# aquaPh.net
KiCad netlist of a schematic drawn in EAGLE
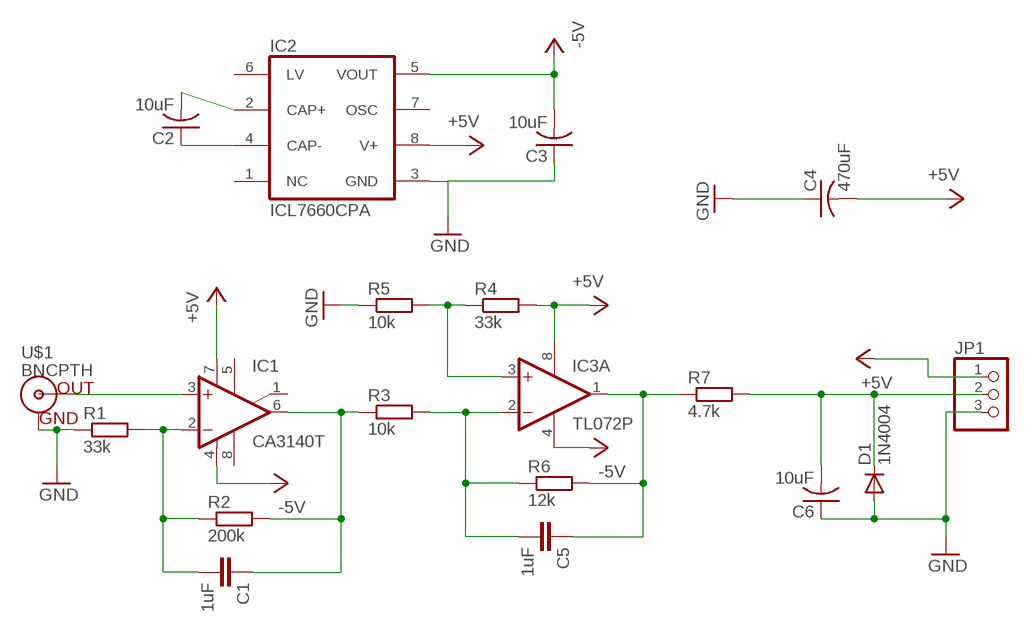
[diagram p0: schematic, sheet 1]

(export (version "E")
  (design (tool "Eeschema 10.0.6"))
  (components
    (comp (ref "C1")
      (value "1uF")
      (footprint "eagle-import:C050-035X075")
      (libsource (lib "eagle-import") (part "C-EU050-035X075"))
    )
    (comp (ref "C2")
      (value "10uF")
      (footprint "eagle-import:C075-042X103")
      (libsource (lib "eagle-import") (part "C-US075-042X103"))
    )
    (comp (ref "C3")
      (value "10uF")
      (footprint "eagle-import:C075-042X103")
      (libsource (lib "eagle-import") (part "C-US075-042X103"))
    )
    (comp (ref "C4")
      (value "470uF")
      (footprint "eagle-import:C075-042X103")
      (libsource (lib "eagle-import") (part "C-US075-042X103"))
    )
    (comp (ref "C5")
      (value "1uF")
      (footprint "eagle-import:C050-035X075")
      (libsource (lib "eagle-import") (part "C-EU050-035X075"))
    )
    (comp (ref "C6")
      (value "10uF")
      (footprint "eagle-import:C075-042X103")
      (libsource (lib "eagle-import") (part "C-US075-042X103"))
    )
    (comp (ref "D1")
      (value "1N4004")
      (footprint "eagle-import:DO41-10")
      (libsource (lib "eagle-import") (part "1N4004"))
    )
    (comp (ref "IC1")
      (value "CA3140T")
      (footprint "eagle-import:TO99")
      (libsource (lib "eagle-import") (part "CA3140T"))
    )
    (comp (ref "IC2")
      (value "ICL7660CPA")
      (footprint "eagle-import:DIL08")
      (fields (field (name "MF") "INTERSIL"))
      (libsource (lib "eagle-import") (part "ICL7660CPA"))
    )
    (comp (ref "IC3")
      (value "TL072P")
      (footprint "eagle-import:DIL08")
      (libsource (lib "eagle-import") (part "TL072P"))
    )
    (comp (ref "JP1")
      (value "PINHD-1X3")
      (footprint "eagle-import:1X03")
      (libsource (lib "eagle-import") (part "PINHD-1X3"))
    )
    (comp (ref "R1")
      (value "33k")
      (footprint "eagle-import:0204_5")
      (libsource (lib "eagle-import") (part "R-EU_0204/5"))
    )
    (comp (ref "R2")
      (value "200k")
      (footprint "eagle-import:0204_5")
      (libsource (lib "eagle-import") (part "R-EU_0204/5"))
    )
    (comp (ref "R3")
      (value "10k")
      (footprint "eagle-import:0204_5")
      (libsource (lib "eagle-import") (part "R-EU_0204/5"))
    )
    (comp (ref "R4")
      (value "33k")
      (footprint "eagle-import:0204_5")
      (libsource (lib "eagle-import") (part "R-EU_0204/5"))
    )
    (comp (ref "R5")
      (value "10k")
      (footprint "eagle-import:0204_5")
      (libsource (lib "eagle-import") (part "R-EU_0204/5"))
    )
    (comp (ref "R6")
      (value "12k")
      (footprint "eagle-import:0204_5")
      (libsource (lib "eagle-import") (part "R-EU_0204/5"))
    )
    (comp (ref "R7")
      (value "4.7k")
      (footprint "eagle-import:0204_5")
      (libsource (lib "eagle-import") (part "R-EU_0204/5"))
    )
    (comp (ref "U$1")
      (value "BNCPTH")
      (footprint "eagle-import:BNC")
      (libsource (lib "eagle-import") (part "BNCPTH"))
    )
  )
  (nets
    (net (code "1") (name "+5V") (class "Default")
      (node (ref "C4") (pin "2") (pinfunction "2_2") (pintype "passive"))
      (node (ref "IC1") (pin "7") (pinfunction "V+_7") (pintype "power_in"))
      (node (ref "IC2") (pin "8") (pinfunction "V+_8") (pintype "power_in"))
      (node (ref "IC3") (pin "8") (pinfunction "V+_8") (pintype "power_in"))
      (node (ref "JP1") (pin "1") (pinfunction "1_1") (pintype "passive"))
      (node (ref "R4") (pin "2") (pinfunction "2_2") (pintype "passive"))
    )
    (net (code "2") (name "-5V") (class "Default")
      (node (ref "C3") (pin "2") (pinfunction "2_2") (pintype "passive"))
      (node (ref "IC1") (pin "4") (pinfunction "V-_4") (pintype "power_in"))
      (node (ref "IC2") (pin "5") (pinfunction "VOUT_5") (pintype "output"))
      (node (ref "IC3") (pin "4") (pinfunction "V-_4") (pintype "power_in"))
    )
    (net (code "3") (name "GND") (class "Default")
      (node (ref "C3") (pin "1") (pinfunction "1_1") (pintype "passive"))
      (node (ref "C4") (pin "1") (pinfunction "1_1") (pintype "passive"))
      (node (ref "C6") (pin "1") (pinfunction "1_1") (pintype "passive"))
      (node (ref "D1") (pin "A") (pinfunction "A_A") (pintype "passive"))
      (node (ref "IC2") (pin "3") (pinfunction "GND_3") (pintype "power_in"))
      (node (ref "JP1") (pin "3") (pinfunction "3_3") (pintype "passive"))
      (node (ref "R1") (pin "1") (pinfunction "1_1") (pintype "passive"))
      (node (ref "R5") (pin "1") (pinfunction "1_1") (pintype "passive"))
      (node (ref "U$1") (pin "GND") (pinfunction "GND_GND") (pintype "bidirectional"))
    )
    (net (code "4") (name "Net-(C6-Pad2)") (class "Default")
      (node (ref "C6") (pin "2") (pinfunction "2_2") (pintype "passive"))
      (node (ref "D1") (pin "C") (pinfunction "C_C") (pintype "passive"))
      (node (ref "JP1") (pin "2") (pinfunction "2_2") (pintype "passive"))
      (node (ref "R7") (pin "2") (pinfunction "2_2") (pintype "passive"))
    )
    (net (code "5") (name "Net-(IC1-+IN)") (class "Default")
      (node (ref "IC1") (pin "3") (pinfunction "+IN_3") (pintype "input"))
      (node (ref "U$1") (pin "S") (pinfunction "OUT_S") (pintype "bidirectional"))
    )
    (net (code "6") (name "Net-(IC1--IN)") (class "Default")
      (node (ref "C1") (pin "2") (pinfunction "2_2") (pintype "passive"))
      (node (ref "IC1") (pin "2") (pinfunction "-IN_2") (pintype "input"))
      (node (ref "R1") (pin "2") (pinfunction "2_2") (pintype "passive"))
      (node (ref "R2") (pin "1") (pinfunction "1_1") (pintype "passive"))
    )
    (net (code "7") (name "Net-(IC1-OUT)") (class "Default")
      (node (ref "C1") (pin "1") (pinfunction "1_1") (pintype "passive"))
      (node (ref "IC1") (pin "6") (pinfunction "OUT_6") (pintype "output"))
      (node (ref "R2") (pin "2") (pinfunction "2_2") (pintype "passive"))
      (node (ref "R3") (pin "1") (pinfunction "1_1") (pintype "passive"))
    )
    (net (code "8") (name "Net-(IC2-CAP+)") (class "Default")
      (node (ref "C2") (pin "2") (pinfunction "2_2") (pintype "passive"))
      (node (ref "IC2") (pin "2") (pinfunction "CAP+_2") (pintype "passive"))
    )
    (net (code "9") (name "Net-(IC2-CAP-)") (class "Default")
      (node (ref "C2") (pin "1") (pinfunction "1_1") (pintype "passive"))
      (node (ref "IC2") (pin "4") (pinfunction "CAP-_4") (pintype "passive"))
    )
    (net (code "10") (name "Net-(IC3A-+IN)") (class "Default")
      (node (ref "IC3") (pin "3") (pinfunction "+IN_3") (pintype "input"))
      (node (ref "R4") (pin "1") (pinfunction "1_1") (pintype "passive"))
      (node (ref "R5") (pin "2") (pinfunction "2_2") (pintype "passive"))
    )
    (net (code "11") (name "Net-(IC3A--IN)") (class "Default")
      (node (ref "C5") (pin "2") (pinfunction "2_2") (pintype "passive"))
      (node (ref "IC3") (pin "2") (pinfunction "-IN_2") (pintype "input"))
      (node (ref "R3") (pin "2") (pinfunction "2_2") (pintype "passive"))
      (node (ref "R6") (pin "1") (pinfunction "1_1") (pintype "passive"))
    )
    (net (code "12") (name "Net-(IC3A-OUT)") (class "Default")
      (node (ref "C5") (pin "1") (pinfunction "1_1") (pintype "passive"))
      (node (ref "IC3") (pin "1") (pinfunction "OUT_1") (pintype "output"))
      (node (ref "R6") (pin "2") (pinfunction "2_2") (pintype "passive"))
      (node (ref "R7") (pin "1") (pinfunction "1_1") (pintype "passive"))
    )
    (net (code "13") (name "unconnected-(IC1-CMP-Pad8)") (class "Default")
      (node (ref "IC1") (pin "8") (pinfunction "CMP_8") (pintype "passive"))
    )
    (net (code "14") (name "unconnected-(IC1-ON-Pad5)") (class "Default")
      (node (ref "IC1") (pin "5") (pinfunction "ON_5") (pintype "passive"))
    )
    (net (code "15") (name "unconnected-(IC1-ON{slash}CMP-Pad1)") (class "Default")
      (node (ref "IC1") (pin "1") (pinfunction "ON/CMP_1") (pintype "passive"))
    )
    (net (code "16") (name "unconnected-(IC2-LV-Pad6)") (class "Default")
      (node (ref "IC2") (pin "6") (pinfunction "LV_6") (pintype "passive"))
    )
    (net (code "17") (name "unconnected-(IC2-NC-Pad1)") (class "Default")
      (node (ref "IC2") (pin "1") (pinfunction "NC_1") (pintype "no_connect"))
    )
    (net (code "18") (name "unconnected-(IC2-OSC-Pad7)") (class "Default")
      (node (ref "IC2") (pin "7") (pinfunction "OSC_7") (pintype "output"))
    )
  )
)
